# SCH_AP-Controller_EasyEDA.net
KiCad netlist of a schematic drawn in EasyEDA
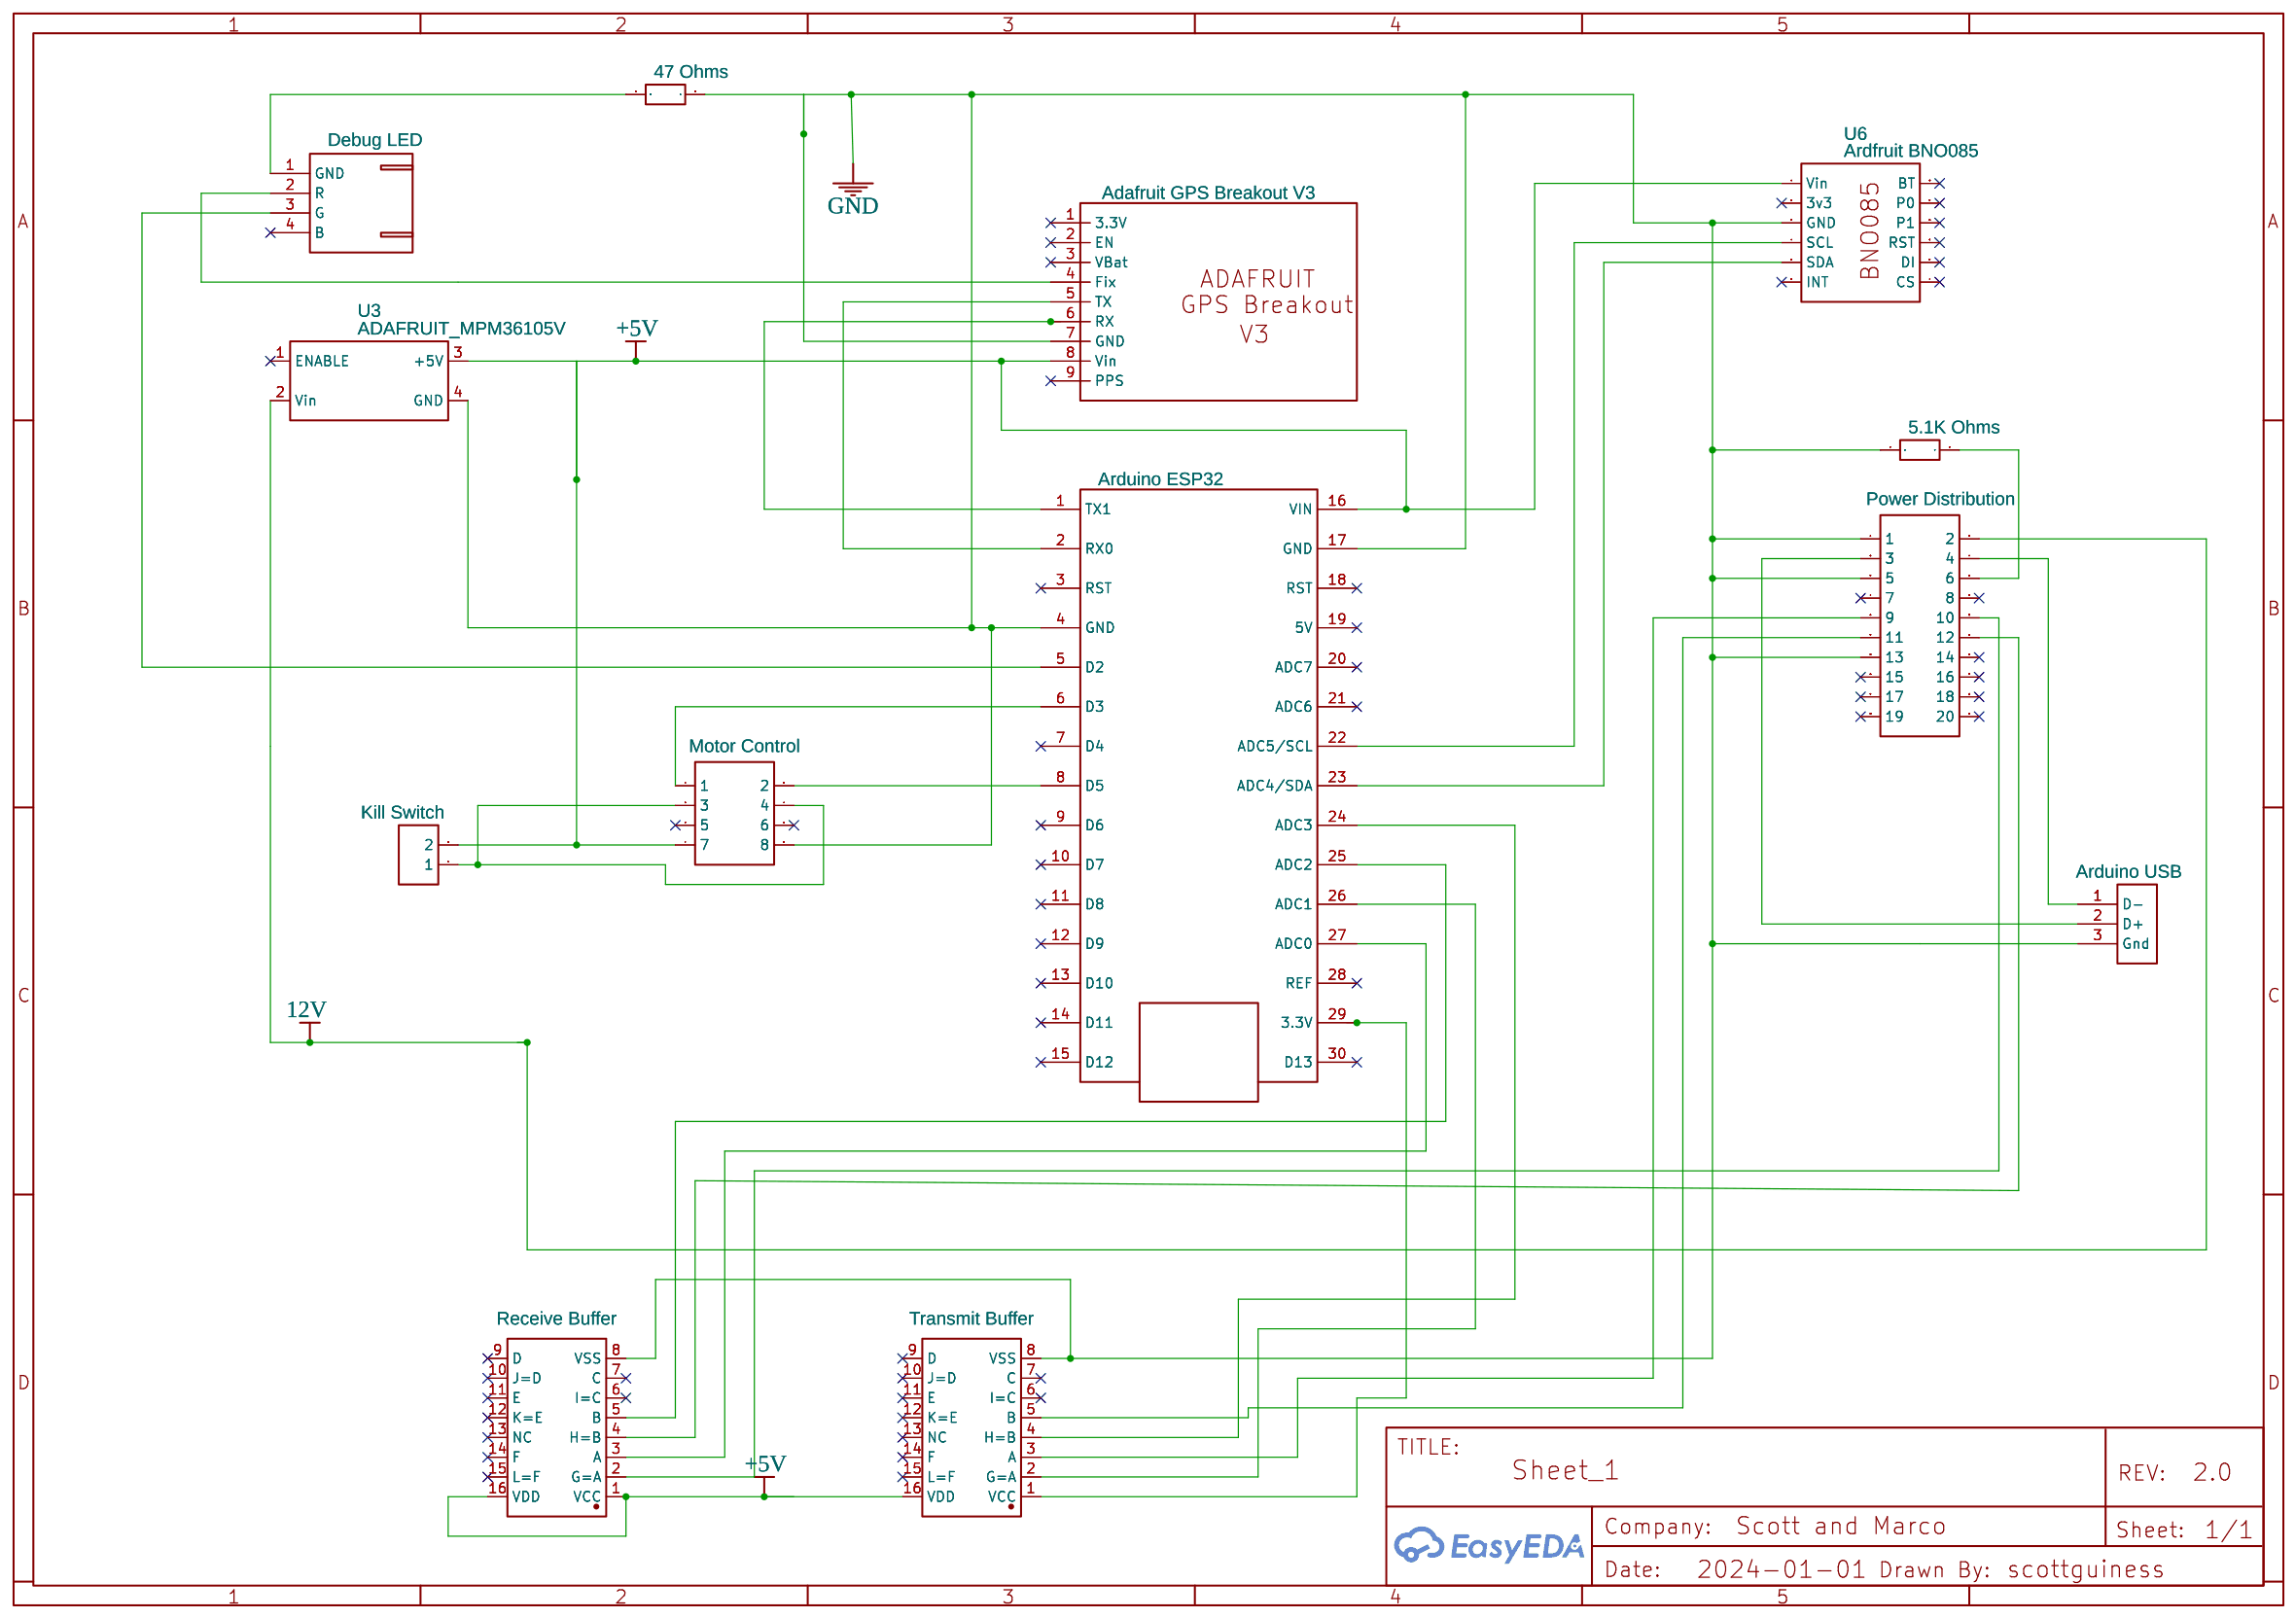
[diagram p0: schematic sheet]

(export (version "E")
  (design (tool "Eeschema 10.0.6"))
  (components
    (comp (ref "HDR-M-2.54_2X4") (value "Motor Control") (libsource (lib "") (part "HDR-M-2.54_2x4")))
    (comp (ref "JST-XH-4-PIN") (value "Debug LED") (libsource (lib "") (part "JST-XH-4-Pin")))
    (comp (ref "JST_XH2.54_2P")
      (value "Kill Switch")
      (fields (field (name "Manufacturer Part") "JST_XH2.54_2P"))
      (libsource (lib "") (part "JST_XH2.54_2P"))
    )
    (comp (ref "JST_XH_1X3") (value "Arduino USB") (libsource (lib "") (part "JST XH 1x3")))
    (comp (ref "POWER1") (value "Power Distribution") (libsource (lib "") (part "HDR-M-2.54_2x10")))
    (comp (ref "R1") (value "47 Ohms") (libsource (lib "") (part "1w resistor")))
    (comp (ref "R2") (value "5.1K Ohms") (libsource (lib "") (part "1w resistor")))
    (comp (ref "U1") (value "Arduino ESP32") (libsource (lib "") (part "ARDUINO_NANO_R3")))
    (comp (ref "U2")
      (value "Transmit Buffer")
      (fields (field (name "Manufacturer Part") "CD4010BE") (field (name "Manufacturer") "TI(德州仪器)"))
      (libsource (lib "") (part "CD4010BE"))
    )
    (comp (ref "U3") (value "ADAFRUIT_MPM36105V") (libsource (lib "") (part "ADAFRUIT_MPM36105V")))
    (comp (ref "U4")
      (value "Adafruit GPS Breakout V3")
      (fields (field (name "Manufacturer Part") "New SchematicLib"))
      (libsource (lib "") (part "Adafruit GPS Breakout V3"))
    )
    (comp (ref "U5")
      (value "Receive Buffer")
      (fields (field (name "Manufacturer Part") "CD4010BE") (field (name "Manufacturer") "TI(德州仪器)"))
      (libsource (lib "") (part "CD4010BE"))
    )
    (comp (ref "U6")
      (value "Ardfruit BNO085")
      (fields (field (name "Manufacturer") "Ardfruit"))
      (libsource (lib "") (part "Ardfruit BNO085"))
    )
  )
  (nets
    (net (code "1") (name "+5V") (class "Default")
      (node (ref "HDR-M-2.54_2X4") (pin "7") (pinfunction "7_7") (pintype "unspecified"))
      (node (ref "JST_XH2.54_2P") (pin "2") (pinfunction "2_2") (pintype "unspecified"))
      (node (ref "U1") (pin "16") (pinfunction "VIN_16") (pintype "unspecified"))
      (node (ref "U2") (pin "16") (pinfunction "VDD_16") (pintype "unspecified"))
      (node (ref "U3") (pin "3") (pinfunction "+5V_3") (pintype "unspecified"))
      (node (ref "U4") (pin "8") (pinfunction "Vin_8") (pintype "unspecified"))
      (node (ref "U5") (pin "1") (pinfunction "VCC_1") (pintype "unspecified"))
      (node (ref "U5") (pin "16") (pinfunction "VDD_16") (pintype "unspecified"))
      (node (ref "U6") (pin "1") (pinfunction "Vin_1") (pintype "unspecified"))
    )
    (net (code "2") (name "12V") (class "Default")
      (node (ref "POWER1") (pin "2") (pinfunction "2_2") (pintype "unspecified"))
      (node (ref "U3") (pin "2") (pinfunction "Vin_2") (pintype "unspecified"))
    )
    (net (code "3") (name "GND") (class "Default")
      (node (ref "HDR-M-2.54_2X4") (pin "8") (pinfunction "8_8") (pintype "unspecified"))
      (node (ref "JST_XH_1X3") (pin "3") (pinfunction "Gnd_3") (pintype "unspecified"))
      (node (ref "POWER1") (pin "1") (pinfunction "1_1") (pintype "unspecified"))
      (node (ref "POWER1") (pin "13") (pinfunction "13_13") (pintype "unspecified"))
      (node (ref "POWER1") (pin "5") (pinfunction "5_5") (pintype "unspecified"))
      (node (ref "R1") (pin "2") (pinfunction "1_2") (pintype "unspecified"))
      (node (ref "R2") (pin "1") (pinfunction "2_1") (pintype "unspecified"))
      (node (ref "U1") (pin "17") (pinfunction "GND_17") (pintype "unspecified"))
      (node (ref "U1") (pin "4") (pinfunction "GND_4") (pintype "unspecified"))
      (node (ref "U2") (pin "8") (pinfunction "VSS_8") (pintype "unspecified"))
      (node (ref "U3") (pin "4") (pinfunction "GND_4") (pintype "unspecified"))
      (node (ref "U4") (pin "7") (pinfunction "GND_7") (pintype "unspecified"))
      (node (ref "U5") (pin "8") (pinfunction "VSS_8") (pintype "unspecified"))
      (node (ref "U6") (pin "3") (pinfunction "GND_3") (pintype "unspecified"))
    )
    (net (code "4") (name "Net-(HDR-M-2.54_2X4-Pad3)") (class "Default")
      (node (ref "HDR-M-2.54_2X4") (pin "3") (pinfunction "3_3") (pintype "unspecified"))
      (node (ref "HDR-M-2.54_2X4") (pin "4") (pinfunction "4_4") (pintype "unspecified"))
      (node (ref "JST_XH2.54_2P") (pin "1") (pinfunction "1_1") (pintype "unspecified"))
    )
    (net (code "5") (name "Net-(JST-XH-4-PIN-G)") (class "Default")
      (node (ref "JST-XH-4-PIN") (pin "3") (pinfunction "G_3") (pintype "unspecified"))
      (node (ref "U1") (pin "5") (pinfunction "D2_5") (pintype "unspecified"))
    )
    (net (code "6") (name "Net-(JST-XH-4-PIN-GND)") (class "Default")
      (node (ref "JST-XH-4-PIN") (pin "1") (pinfunction "GND_1") (pintype "unspecified"))
      (node (ref "R1") (pin "1") (pinfunction "2_1") (pintype "unspecified"))
    )
    (net (code "7") (name "Net-(JST-XH-4-PIN-R)") (class "Default")
      (node (ref "JST-XH-4-PIN") (pin "2") (pinfunction "R_2") (pintype "unspecified"))
      (node (ref "U4") (pin "4") (pinfunction "Fix_4") (pintype "unspecified"))
    )
    (net (code "8") (name "Net-(JST_XH_1X3-D+)") (class "Default")
      (node (ref "JST_XH_1X3") (pin "2") (pinfunction "D+_2") (pintype "unspecified"))
      (node (ref "POWER1") (pin "3") (pinfunction "3_3") (pintype "unspecified"))
    )
    (net (code "9") (name "Net-(JST_XH_1X3-D-)") (class "Default")
      (node (ref "JST_XH_1X3") (pin "1") (pinfunction "D-_1") (pintype "unspecified"))
      (node (ref "POWER1") (pin "4") (pinfunction "4_4") (pintype "unspecified"))
    )
    (net (code "10") (name "Net-(R2-1)") (class "Default")
      (node (ref "POWER1") (pin "6") (pinfunction "6_6") (pintype "unspecified"))
      (node (ref "R2") (pin "2") (pinfunction "1_2") (pintype "unspecified"))
    )
    (net (code "11") (name "Net-(U1-3.3V)") (class "Default")
      (node (ref "U1") (pin "29") (pinfunction "3.3V_29") (pintype "unspecified"))
      (node (ref "U2") (pin "1") (pinfunction "VCC_1") (pintype "unspecified"))
    )
    (net (code "12") (name "Net-(U1-ADC0)") (class "Default")
      (node (ref "U1") (pin "27") (pinfunction "ADC0_27") (pintype "unspecified"))
      (node (ref "U5") (pin "3") (pinfunction "A_3") (pintype "unspecified"))
    )
    (net (code "13") (name "Net-(U1-ADC1)") (class "Default")
      (node (ref "U1") (pin "26") (pinfunction "ADC1_26") (pintype "unspecified"))
      (node (ref "U2") (pin "2") (pinfunction "G=A_2") (pintype "unspecified"))
    )
    (net (code "14") (name "Net-(U1-ADC2)") (class "Default")
      (node (ref "U1") (pin "25") (pinfunction "ADC2_25") (pintype "unspecified"))
      (node (ref "U5") (pin "5") (pinfunction "B_5") (pintype "unspecified"))
    )
    (net (code "15") (name "Net-(U1-ADC3)") (class "Default")
      (node (ref "U1") (pin "24") (pinfunction "ADC3_24") (pintype "unspecified"))
      (node (ref "U2") (pin "4") (pinfunction "H=B_4") (pintype "unspecified"))
    )
    (net (code "16") (name "Net-(U1-ADC4{slash}SDA)") (class "Default")
      (node (ref "U1") (pin "23") (pinfunction "ADC4/SDA_23") (pintype "unspecified"))
      (node (ref "U6") (pin "5") (pinfunction "SDA_5") (pintype "unspecified"))
    )
    (net (code "17") (name "Net-(U1-ADC5{slash}SCL)") (class "Default")
      (node (ref "U1") (pin "22") (pinfunction "ADC5/SCL_22") (pintype "unspecified"))
      (node (ref "U6") (pin "4") (pinfunction "SCL_4") (pintype "unspecified"))
    )
    (net (code "18") (name "Net-(U1-D3)") (class "Default")
      (node (ref "HDR-M-2.54_2X4") (pin "1") (pinfunction "1_1") (pintype "unspecified"))
      (node (ref "U1") (pin "6") (pinfunction "D3_6") (pintype "unspecified"))
    )
    (net (code "19") (name "Net-(U1-D5)") (class "Default")
      (node (ref "HDR-M-2.54_2X4") (pin "2") (pinfunction "2_2") (pintype "unspecified"))
      (node (ref "U1") (pin "8") (pinfunction "D5_8") (pintype "unspecified"))
    )
    (net (code "20") (name "Net-(U1-RX0)") (class "Default")
      (node (ref "U1") (pin "2") (pinfunction "RX0_2") (pintype "unspecified"))
      (node (ref "U4") (pin "5") (pinfunction "TX_5") (pintype "unspecified"))
    )
    (net (code "21") (name "Net-(U1-TX1)") (class "Default")
      (node (ref "U1") (pin "1") (pinfunction "TX1_1") (pintype "unspecified"))
      (node (ref "U4") (pin "6") (pinfunction "RX_6") (pintype "unspecified"))
    )
    (net (code "22") (name "Net-(U2-A)") (class "Default")
      (node (ref "POWER1") (pin "9") (pinfunction "9_9") (pintype "unspecified"))
      (node (ref "U2") (pin "3") (pinfunction "A_3") (pintype "unspecified"))
    )
    (net (code "23") (name "Net-(U2-B)") (class "Default")
      (node (ref "POWER1") (pin "11") (pinfunction "11_11") (pintype "unspecified"))
      (node (ref "U2") (pin "5") (pinfunction "B_5") (pintype "unspecified"))
    )
    (net (code "24") (name "Net-(U5-G=A)") (class "Default")
      (node (ref "POWER1") (pin "10") (pinfunction "10_10") (pintype "unspecified"))
      (node (ref "U5") (pin "2") (pinfunction "G=A_2") (pintype "unspecified"))
    )
    (net (code "25") (name "Net-(U5-H=B)") (class "Default")
      (node (ref "POWER1") (pin "12") (pinfunction "12_12") (pintype "unspecified"))
      (node (ref "U5") (pin "4") (pinfunction "H=B_4") (pintype "unspecified"))
    )
    (net (code "26") (name "unconnected-(HDR-M-2.54_2X4-Pad5)") (class "Default")
      (node (ref "HDR-M-2.54_2X4") (pin "5") (pinfunction "5_5") (pintype "unspecified+no_connect"))
    )
    (net (code "27") (name "unconnected-(HDR-M-2.54_2X4-Pad6)") (class "Default")
      (node (ref "HDR-M-2.54_2X4") (pin "6") (pinfunction "6_6") (pintype "unspecified+no_connect"))
    )
    (net (code "28") (name "unconnected-(JST-XH-4-PIN-B-Pad4)") (class "Default")
      (node (ref "JST-XH-4-PIN") (pin "4") (pinfunction "B_4") (pintype "unspecified+no_connect"))
    )
    (net (code "29") (name "unconnected-(POWER1-Pad7)") (class "Default")
      (node (ref "POWER1") (pin "7") (pinfunction "7_7") (pintype "unspecified+no_connect"))
    )
    (net (code "30") (name "unconnected-(POWER1-Pad8)") (class "Default")
      (node (ref "POWER1") (pin "8") (pinfunction "8_8") (pintype "unspecified+no_connect"))
    )
    (net (code "31") (name "unconnected-(POWER1-Pad14)") (class "Default")
      (node (ref "POWER1") (pin "14") (pinfunction "14_14") (pintype "unspecified+no_connect"))
    )
    (net (code "32") (name "unconnected-(POWER1-Pad15)") (class "Default")
      (node (ref "POWER1") (pin "15") (pinfunction "15_15") (pintype "unspecified+no_connect"))
    )
    (net (code "33") (name "unconnected-(POWER1-Pad16)") (class "Default")
      (node (ref "POWER1") (pin "16") (pinfunction "16_16") (pintype "unspecified+no_connect"))
    )
    (net (code "34") (name "unconnected-(POWER1-Pad17)") (class "Default")
      (node (ref "POWER1") (pin "17") (pinfunction "17_17") (pintype "unspecified+no_connect"))
    )
    (net (code "35") (name "unconnected-(POWER1-Pad18)") (class "Default")
      (node (ref "POWER1") (pin "18") (pinfunction "18_18") (pintype "unspecified+no_connect"))
    )
    (net (code "36") (name "unconnected-(POWER1-Pad19)") (class "Default")
      (node (ref "POWER1") (pin "19") (pinfunction "19_19") (pintype "unspecified+no_connect"))
    )
    (net (code "37") (name "unconnected-(POWER1-Pad20)") (class "Default")
      (node (ref "POWER1") (pin "20") (pinfunction "20_20") (pintype "unspecified+no_connect"))
    )
    (net (code "38") (name "unconnected-(U1-5V-Pad19)") (class "Default")
      (node (ref "U1") (pin "19") (pinfunction "5V_19") (pintype "unspecified+no_connect"))
    )
    (net (code "39") (name "unconnected-(U1-ADC6-Pad21)") (class "Default")
      (node (ref "U1") (pin "21") (pinfunction "ADC6_21") (pintype "unspecified+no_connect"))
    )
    (net (code "40") (name "unconnected-(U1-ADC7-Pad20)") (class "Default")
      (node (ref "U1") (pin "20") (pinfunction "ADC7_20") (pintype "unspecified+no_connect"))
    )
    (net (code "41") (name "unconnected-(U1-D4-Pad7)") (class "Default")
      (node (ref "U1") (pin "7") (pinfunction "D4_7") (pintype "unspecified+no_connect"))
    )
    (net (code "42") (name "unconnected-(U1-D6-Pad9)") (class "Default")
      (node (ref "U1") (pin "9") (pinfunction "D6_9") (pintype "unspecified+no_connect"))
    )
    (net (code "43") (name "unconnected-(U1-D7-Pad10)") (class "Default")
      (node (ref "U1") (pin "10") (pinfunction "D7_10") (pintype "unspecified+no_connect"))
    )
    (net (code "44") (name "unconnected-(U1-D8-Pad11)") (class "Default")
      (node (ref "U1") (pin "11") (pinfunction "D8_11") (pintype "unspecified+no_connect"))
    )
    (net (code "45") (name "unconnected-(U1-D9-Pad12)") (class "Default")
      (node (ref "U1") (pin "12") (pinfunction "D9_12") (pintype "unspecified+no_connect"))
    )
    (net (code "46") (name "unconnected-(U1-D10-Pad13)") (class "Default")
      (node (ref "U1") (pin "13") (pinfunction "D10_13") (pintype "unspecified+no_connect"))
    )
    (net (code "47") (name "unconnected-(U1-D11-Pad14)") (class "Default")
      (node (ref "U1") (pin "14") (pinfunction "D11_14") (pintype "unspecified+no_connect"))
    )
    (net (code "48") (name "unconnected-(U1-D12-Pad15)") (class "Default")
      (node (ref "U1") (pin "15") (pinfunction "D12_15") (pintype "unspecified+no_connect"))
    )
    (net (code "49") (name "unconnected-(U1-D13-Pad30)") (class "Default")
      (node (ref "U1") (pin "30") (pinfunction "D13_30") (pintype "unspecified+no_connect"))
    )
    (net (code "50") (name "unconnected-(U1-REF-Pad28)") (class "Default")
      (node (ref "U1") (pin "28") (pinfunction "REF_28") (pintype "unspecified+no_connect"))
    )
    (net (code "51") (name "unconnected-(U1-RST-Pad3)") (class "Default")
      (node (ref "U1") (pin "3") (pinfunction "RST_3") (pintype "unspecified+no_connect"))
    )
    (net (code "52") (name "unconnected-(U1-RST-Pad18)") (class "Default")
      (node (ref "U1") (pin "18") (pinfunction "RST_18") (pintype "unspecified+no_connect"))
    )
    (net (code "53") (name "unconnected-(U2-C-Pad7)") (class "Default")
      (node (ref "U2") (pin "7") (pinfunction "C_7") (pintype "unspecified+no_connect"))
    )
    (net (code "54") (name "unconnected-(U2-D-Pad9)") (class "Default")
      (node (ref "U2") (pin "9") (pinfunction "D_9") (pintype "unspecified+no_connect"))
    )
    (net (code "55") (name "unconnected-(U2-E-Pad11)") (class "Default")
      (node (ref "U2") (pin "11") (pinfunction "E_11") (pintype "unspecified+no_connect"))
    )
    (net (code "56") (name "unconnected-(U2-F-Pad14)") (class "Default")
      (node (ref "U2") (pin "14") (pinfunction "F_14") (pintype "unspecified+no_connect"))
    )
    (net (code "57") (name "unconnected-(U2-I=C-Pad6)") (class "Default")
      (node (ref "U2") (pin "6") (pinfunction "I=C_6") (pintype "unspecified+no_connect"))
    )
    (net (code "58") (name "unconnected-(U2-J=D-Pad10)") (class "Default")
      (node (ref "U2") (pin "10") (pinfunction "J=D_10") (pintype "unspecified+no_connect"))
    )
    (net (code "59") (name "unconnected-(U2-K=E-Pad12)") (class "Default")
      (node (ref "U2") (pin "12") (pinfunction "K=E_12") (pintype "unspecified+no_connect"))
    )
    (net (code "60") (name "unconnected-(U2-L=F-Pad15)") (class "Default")
      (node (ref "U2") (pin "15") (pinfunction "L=F_15") (pintype "unspecified+no_connect"))
    )
    (net (code "61") (name "unconnected-(U2-NC-Pad13)") (class "Default")
      (node (ref "U2") (pin "13") (pinfunction "NC_13") (pintype "unspecified+no_connect"))
    )
    (net (code "62") (name "unconnected-(U3-ENABLE-Pad1)") (class "Default")
      (node (ref "U3") (pin "1") (pinfunction "ENABLE_1") (pintype "unspecified+no_connect"))
    )
    (net (code "63") (name "unconnected-(U4-3.3V-Pad1)") (class "Default")
      (node (ref "U4") (pin "1") (pinfunction "3.3V_1") (pintype "unspecified+no_connect"))
    )
    (net (code "64") (name "unconnected-(U4-EN-Pad2)") (class "Default")
      (node (ref "U4") (pin "2") (pinfunction "EN_2") (pintype "unspecified+no_connect"))
    )
    (net (code "65") (name "unconnected-(U4-PPS-Pad9)") (class "Default")
      (node (ref "U4") (pin "9") (pinfunction "PPS_9") (pintype "unspecified+no_connect"))
    )
    (net (code "66") (name "unconnected-(U4-VBat-Pad3)") (class "Default")
      (node (ref "U4") (pin "3") (pinfunction "VBat_3") (pintype "unspecified+no_connect"))
    )
    (net (code "67") (name "unconnected-(U5-C-Pad7)") (class "Default")
      (node (ref "U5") (pin "7") (pinfunction "C_7") (pintype "unspecified+no_connect"))
    )
    (net (code "68") (name "unconnected-(U5-D-Pad9)") (class "Default")
      (node (ref "U5") (pin "9") (pinfunction "D_9") (pintype "unspecified+no_connect"))
    )
    (net (code "69") (name "unconnected-(U5-E-Pad11)") (class "Default")
      (node (ref "U5") (pin "11") (pinfunction "E_11") (pintype "unspecified+no_connect"))
    )
    (net (code "70") (name "unconnected-(U5-F-Pad14)") (class "Default")
      (node (ref "U5") (pin "14") (pinfunction "F_14") (pintype "unspecified+no_connect"))
    )
    (net (code "71") (name "unconnected-(U5-I=C-Pad6)") (class "Default")
      (node (ref "U5") (pin "6") (pinfunction "I=C_6") (pintype "unspecified+no_connect"))
    )
    (net (code "72") (name "unconnected-(U5-J=D-Pad10)") (class "Default")
      (node (ref "U5") (pin "10") (pinfunction "J=D_10") (pintype "unspecified+no_connect"))
    )
    (net (code "73") (name "unconnected-(U5-K=E-Pad12)") (class "Default")
      (node (ref "U5") (pin "12") (pinfunction "K=E_12") (pintype "unspecified+no_connect"))
    )
    (net (code "74") (name "unconnected-(U5-L=F-Pad15)") (class "Default")
      (node (ref "U5") (pin "15") (pinfunction "L=F_15") (pintype "unspecified+no_connect"))
    )
    (net (code "75") (name "unconnected-(U5-NC-Pad13)") (class "Default")
      (node (ref "U5") (pin "13") (pinfunction "NC_13") (pintype "unspecified+no_connect"))
    )
    (net (code "76") (name "unconnected-(U6-3v3-Pad2)") (class "Default")
      (node (ref "U6") (pin "2") (pinfunction "3v3_2") (pintype "unspecified+no_connect"))
    )
    (net (code "77") (name "unconnected-(U6-BT-Pad12)") (class "Default")
      (node (ref "U6") (pin "12") (pinfunction "BT_12") (pintype "unspecified+no_connect"))
    )
    (net (code "78") (name "unconnected-(U6-CS-Pad7)") (class "Default")
      (node (ref "U6") (pin "7") (pinfunction "CS_7") (pintype "unspecified+no_connect"))
    )
    (net (code "79") (name "unconnected-(U6-DI-Pad8)") (class "Default")
      (node (ref "U6") (pin "8") (pinfunction "DI_8") (pintype "unspecified+no_connect"))
    )
    (net (code "80") (name "unconnected-(U6-INT-Pad6)") (class "Default")
      (node (ref "U6") (pin "6") (pinfunction "INT_6") (pintype "unspecified+no_connect"))
    )
    (net (code "81") (name "unconnected-(U6-P0-Pad11)") (class "Default")
      (node (ref "U6") (pin "11") (pinfunction "P0_11") (pintype "unspecified+no_connect"))
    )
    (net (code "82") (name "unconnected-(U6-P1-Pad10)") (class "Default")
      (node (ref "U6") (pin "10") (pinfunction "P1_10") (pintype "unspecified+no_connect"))
    )
    (net (code "83") (name "unconnected-(U6-RST-Pad9)") (class "Default")
      (node (ref "U6") (pin "9") (pinfunction "RST_9") (pintype "unspecified+no_connect"))
    )
  )
)
